# esp32_programmer_revA.net
KiCad netlist of a schematic drawn in EAGLE
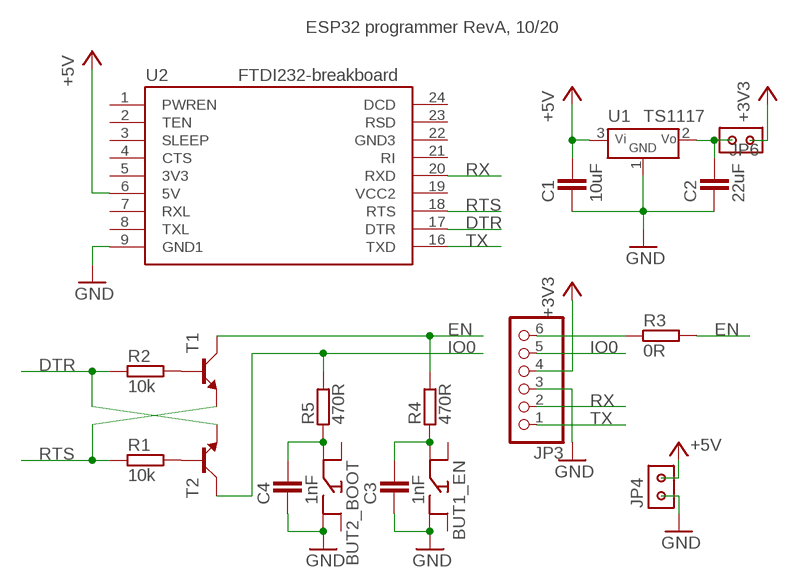
[diagram p0: schematic, sheet 1]

(export (version "E")
  (design (tool "Eeschema 10.0.6"))
  (components
    (comp (ref "BUT1_EN")
      (value "BUTTON'SMD'")
      (footprint "eagle-import:BUTTON_SMD")
      (libsource (lib "eagle-import") (part "BUTTON'SMD'"))
    )
    (comp (ref "BUT2_BOOT")
      (value "BUTTON'SMD'")
      (footprint "eagle-import:BUTTON_SMD")
      (libsource (lib "eagle-import") (part "BUTTON'SMD'"))
    )
    (comp (ref "C1")
      (value "10uF")
      (footprint "eagle-import:C0805")
      (libsource (lib "eagle-import") (part "C-CERAMIC'SMD'"))
    )
    (comp (ref "C2")
      (value "22uF")
      (footprint "eagle-import:C0805")
      (libsource (lib "eagle-import") (part "C-CERAMIC'SMD'"))
    )
    (comp (ref "C3")
      (value "1nF")
      (footprint "eagle-import:C0805")
      (libsource (lib "eagle-import") (part "C-CERAMIC'SMD'"))
    )
    (comp (ref "C4")
      (value "1nF")
      (footprint "eagle-import:C0805")
      (libsource (lib "eagle-import") (part "C-CERAMIC'SMD'"))
    )
    (comp (ref "JP3")
      (value "PINHD-1X6")
      (footprint "eagle-import:1X06")
      (libsource (lib "eagle-import") (part "PINHD-1X6"))
    )
    (comp (ref "JP4")
      (value "PINHD-2X1")
      (footprint "eagle-import:PINHD-2X1")
      (libsource (lib "eagle-import") (part "PINHD-2X1"))
    )
    (comp (ref "JP6")
      (value "PINHD-2X1")
      (footprint "eagle-import:PINHD-2X1")
      (libsource (lib "eagle-import") (part "PINHD-2X1"))
    )
    (comp (ref "R1")
      (value "10k")
      (footprint "eagle-import:R0805")
      (libsource (lib "eagle-import") (part "R'2'"))
    )
    (comp (ref "R2")
      (value "10k")
      (footprint "eagle-import:R0805")
      (libsource (lib "eagle-import") (part "R'2'"))
    )
    (comp (ref "R3")
      (value "0R")
      (footprint "eagle-import:R0805")
      (libsource (lib "eagle-import") (part "R'2'"))
    )
    (comp (ref "R4")
      (value "470R")
      (footprint "eagle-import:R0805")
      (libsource (lib "eagle-import") (part "R'2'"))
    )
    (comp (ref "R5")
      (value "470R")
      (footprint "eagle-import:R0805")
      (libsource (lib "eagle-import") (part "R'2'"))
    )
    (comp (ref "T1")
      (value "TRAN_NPN'BC817'")
      (footprint "eagle-import:SOT23")
      (libsource (lib "eagle-import") (part "TRAN_NPN'BC817'"))
    )
    (comp (ref "T2")
      (value "TRAN_NPN'BC817'")
      (footprint "eagle-import:SOT23")
      (libsource (lib "eagle-import") (part "TRAN_NPN'BC817'"))
    )
    (comp (ref "U1")
      (value "TS1117")
      (footprint "eagle-import:SOT223")
      (libsource (lib "eagle-import") (part "V_STAB'TS1117'"))
    )
    (comp (ref "U2")
      (value "FTDI232-BREAKBOARD-SIMPLE")
      (footprint "eagle-import:FTDI232-BRAKBOARD-SIMPLE")
      (libsource (lib "eagle-import") (part "FTDI232-BREAKBOARD-SIMPLE"))
    )
  )
  (nets
    (net (code "1") (name "+3V3") (class "Default")
      (node (ref "JP3") (pin "4") (pinfunction "4_4") (pintype "passive"))
      (node (ref "JP6") (pin "2") (pinfunction "2_2") (pintype "bidirectional"))
    )
    (net (code "2") (name "+5V") (class "Default")
      (node (ref "C1") (pin "2") (pinfunction "P$2_2") (pintype "bidirectional"))
      (node (ref "JP4") (pin "1") (pinfunction "1_1") (pintype "input"))
      (node (ref "U1") (pin "3") (pinfunction "VIN_3") (pintype "power_in"))
      (node (ref "U2") (pin "6") (pinfunction "5V_6") (pintype "power_in"))
    )
    (net (code "3") (name "/3V3") (class "Default")
      (node (ref "U2") (pin "5") (pinfunction "3V3_5") (pintype "power_in"))
    )
    (net (code "4") (name "/DTR") (class "Default")
      (node (ref "R2") (pin "1") (pinfunction "P$1_1") (pintype "bidirectional"))
      (node (ref "T2") (pin "2") (pinfunction "E_2") (pintype "bidirectional"))
      (node (ref "U2") (pin "17") (pinfunction "DTR_17") (pintype "bidirectional"))
    )
    (net (code "5") (name "/EN") (class "Default")
      (node (ref "R3") (pin "2") (pinfunction "P$2_2") (pintype "bidirectional"))
      (node (ref "R4") (pin "2") (pinfunction "P$2_2") (pintype "bidirectional"))
      (node (ref "T1") (pin "3") (pinfunction "C_3") (pintype "bidirectional"))
    )
    (net (code "6") (name "/GND3") (class "Default")
      (node (ref "U2") (pin "22") (pinfunction "GND3_22") (pintype "power_in"))
    )
    (net (code "7") (name "/IO0") (class "Default")
      (node (ref "JP3") (pin "5") (pinfunction "5_5") (pintype "passive"))
      (node (ref "R5") (pin "2") (pinfunction "P$2_2") (pintype "bidirectional"))
      (node (ref "T2") (pin "3") (pinfunction "C_3") (pintype "bidirectional"))
    )
    (net (code "8") (name "/RTS") (class "Default")
      (node (ref "R1") (pin "1") (pinfunction "P$1_1") (pintype "bidirectional"))
      (node (ref "T1") (pin "2") (pinfunction "E_2") (pintype "bidirectional"))
      (node (ref "U2") (pin "18") (pinfunction "RTS_18") (pintype "bidirectional"))
    )
    (net (code "9") (name "/RX") (class "Default")
      (node (ref "JP3") (pin "2") (pinfunction "2_2") (pintype "passive"))
      (node (ref "U2") (pin "20") (pinfunction "RXD_20") (pintype "bidirectional"))
    )
    (net (code "10") (name "/TX") (class "Default")
      (node (ref "JP3") (pin "1") (pinfunction "1_1") (pintype "passive"))
      (node (ref "U2") (pin "16") (pinfunction "TXD_16") (pintype "bidirectional"))
    )
    (net (code "11") (name "/VCC2") (class "Default")
      (node (ref "U2") (pin "19") (pinfunction "VCC2_19") (pintype "power_in"))
    )
    (net (code "12") (name "GND") (class "Default")
      (node (ref "BUT1_EN") (pin "3") (pinfunction "1_3") (pintype "bidirectional"))
      (node (ref "BUT2_BOOT") (pin "3") (pinfunction "1_3") (pintype "bidirectional"))
      (node (ref "C1") (pin "1") (pinfunction "P$1_1") (pintype "bidirectional"))
      (node (ref "C2") (pin "1") (pinfunction "P$1_1") (pintype "bidirectional"))
      (node (ref "C3") (pin "1") (pinfunction "P$1_1") (pintype "bidirectional"))
      (node (ref "C4") (pin "1") (pinfunction "P$1_1") (pintype "bidirectional"))
      (node (ref "JP3") (pin "3") (pinfunction "3_3") (pintype "passive"))
      (node (ref "JP4") (pin "2") (pinfunction "2_2") (pintype "bidirectional"))
      (node (ref "U1") (pin "1") (pinfunction "GND_1") (pintype "power_in"))
      (node (ref "U2") (pin "9") (pinfunction "GND1_9") (pintype "power_in"))
    )
    (net (code "13") (name "Net-(C2-P$2)") (class "Default")
      (node (ref "C2") (pin "2") (pinfunction "P$2_2") (pintype "bidirectional"))
      (node (ref "JP6") (pin "1") (pinfunction "1_1") (pintype "input"))
      (node (ref "U1") (pin "2") (pinfunction "VOUT_2") (pintype "power_in"))
    )
    (net (code "14") (name "Net-(C3-P$2)") (class "Default")
      (node (ref "BUT1_EN") (pin "2") (pinfunction "2_2") (pintype "bidirectional"))
      (node (ref "C3") (pin "2") (pinfunction "P$2_2") (pintype "bidirectional"))
      (node (ref "R4") (pin "1") (pinfunction "P$1_1") (pintype "bidirectional"))
    )
    (net (code "15") (name "Net-(C4-P$2)") (class "Default")
      (node (ref "BUT2_BOOT") (pin "2") (pinfunction "2_2") (pintype "bidirectional"))
      (node (ref "C4") (pin "2") (pinfunction "P$2_2") (pintype "bidirectional"))
      (node (ref "R5") (pin "1") (pinfunction "P$1_1") (pintype "bidirectional"))
    )
    (net (code "16") (name "Net-(R1-P$2)") (class "Default")
      (node (ref "R1") (pin "2") (pinfunction "P$2_2") (pintype "bidirectional"))
      (node (ref "T2") (pin "1") (pinfunction "B_1") (pintype "bidirectional"))
    )
    (net (code "17") (name "Net-(R2-P$2)") (class "Default")
      (node (ref "R2") (pin "2") (pinfunction "P$2_2") (pintype "bidirectional"))
      (node (ref "T1") (pin "1") (pinfunction "B_1") (pintype "bidirectional"))
    )
    (net (code "18") (name "Net-(R3-P$1)") (class "Default")
      (node (ref "JP3") (pin "6") (pinfunction "6_6") (pintype "passive"))
      (node (ref "R3") (pin "1") (pinfunction "P$1_1") (pintype "bidirectional"))
    )
    (net (code "19") (name "unconnected-(BUT1_EN-3-Pad4)") (class "Default")
      (node (ref "BUT1_EN") (pin "4") (pinfunction "3_4") (pintype "bidirectional"))
    )
    (net (code "20") (name "unconnected-(BUT1_EN-4-Pad1)") (class "Default")
      (node (ref "BUT1_EN") (pin "1") (pinfunction "4_1") (pintype "bidirectional"))
    )
    (net (code "21") (name "unconnected-(BUT2_BOOT-3-Pad4)") (class "Default")
      (node (ref "BUT2_BOOT") (pin "4") (pinfunction "3_4") (pintype "bidirectional"))
    )
    (net (code "22") (name "unconnected-(BUT2_BOOT-4-Pad1)") (class "Default")
      (node (ref "BUT2_BOOT") (pin "1") (pinfunction "4_1") (pintype "bidirectional"))
    )
    (net (code "23") (name "unconnected-(U2-CTS-Pad4)") (class "Default")
      (node (ref "U2") (pin "4") (pinfunction "CTS_4") (pintype "bidirectional"))
    )
    (net (code "24") (name "unconnected-(U2-DCD-Pad24)") (class "Default")
      (node (ref "U2") (pin "24") (pinfunction "DCD_24") (pintype "bidirectional"))
    )
    (net (code "25") (name "unconnected-(U2-PWREN-Pad1)") (class "Default")
      (node (ref "U2") (pin "1") (pinfunction "PWREN_1") (pintype "bidirectional"))
    )
    (net (code "26") (name "unconnected-(U2-RI-Pad21)") (class "Default")
      (node (ref "U2") (pin "21") (pinfunction "RI_21") (pintype "bidirectional"))
    )
    (net (code "27") (name "unconnected-(U2-RSD-Pad23)") (class "Default")
      (node (ref "U2") (pin "23") (pinfunction "RSD_23") (pintype "bidirectional"))
    )
    (net (code "28") (name "unconnected-(U2-RXL-Pad7)") (class "Default")
      (node (ref "U2") (pin "7") (pinfunction "RXL_7") (pintype "bidirectional"))
    )
    (net (code "29") (name "unconnected-(U2-SLEEP-Pad3)") (class "Default")
      (node (ref "U2") (pin "3") (pinfunction "SLEEP_3") (pintype "bidirectional"))
    )
    (net (code "30") (name "unconnected-(U2-TEN-Pad2)") (class "Default")
      (node (ref "U2") (pin "2") (pinfunction "TEN_2") (pintype "bidirectional"))
    )
    (net (code "31") (name "unconnected-(U2-TXL-Pad8)") (class "Default")
      (node (ref "U2") (pin "8") (pinfunction "TXL_8") (pintype "bidirectional"))
    )
  )
)
